# Szymon_Sochaj_schemat2.net
KiCad netlist of a schematic drawn in EAGLE
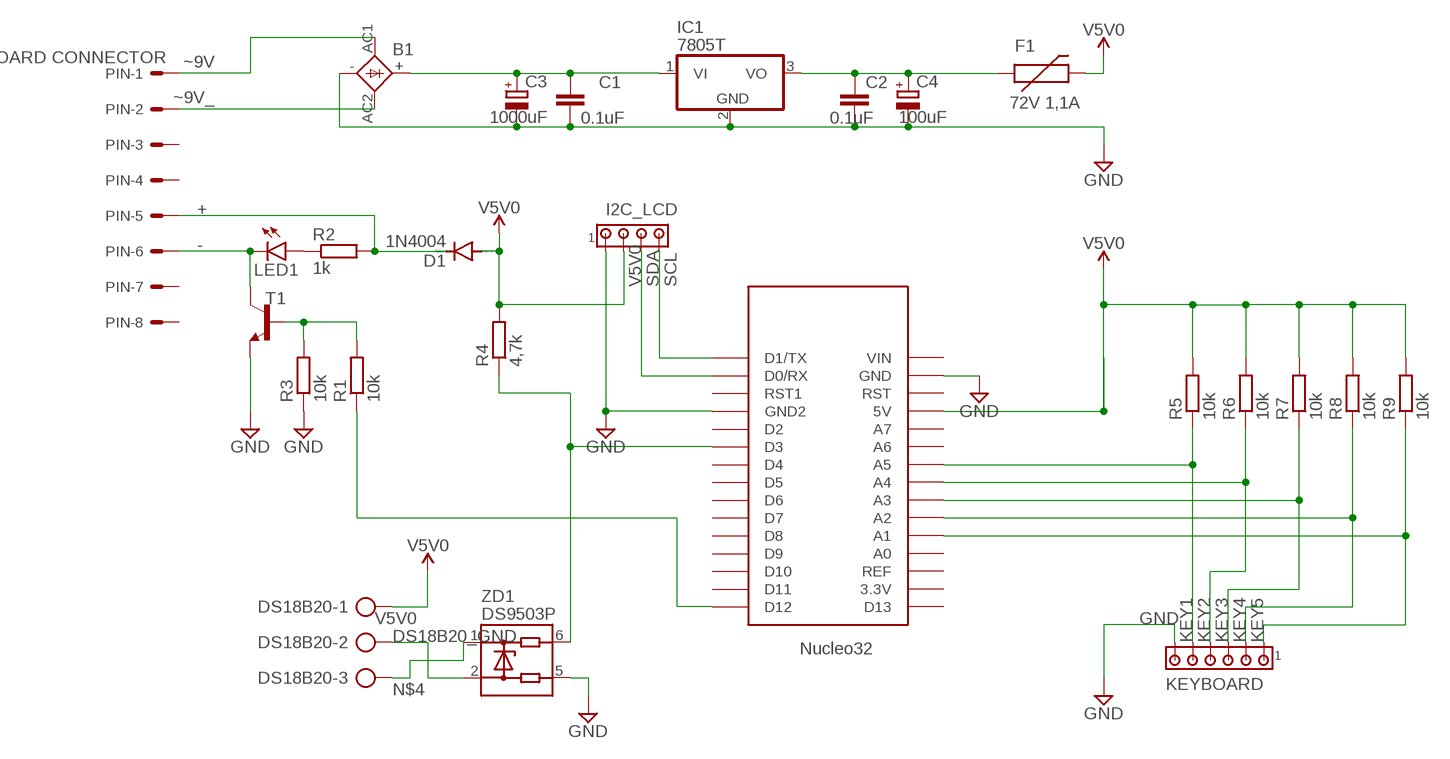
[diagram p0: schematic, sheet 1]

(export (version "E")
  (design (tool "Eeschema 10.0.6"))
  (components
    (comp (ref "B1")
      (value "2KBP")
      (footprint "eagle-import:2KBP")
      (libsource (lib "eagle-import") (part "2KBP"))
    )
    (comp (ref "C1")
      (value "0.1uF")
      (footprint "eagle-import:CAP-PTH-SMALL-KIT")
      (libsource (lib "eagle-import") (part "0.1UF-KIT-EZ-50V-20%"))
    )
    (comp (ref "C2")
      (value "0.1uF")
      (footprint "eagle-import:CAP-PTH-SMALL-KIT")
      (libsource (lib "eagle-import") (part "0.1UF-KIT-EZ-50V-20%"))
    )
    (comp (ref "C3")
      (value "1000uF")
      (footprint "eagle-import:CAPPRD550W60D1200H2000B")
      (libsource (lib "eagle-import") (part "C-POLRADIAL-20MM-DIA"))
    )
    (comp (ref "C4")
      (value "100uF")
      (footprint "eagle-import:CAPPRD550W60D1200H2000B")
      (libsource (lib "eagle-import") (part "C-POLRADIAL-20MM-DIA_"))
    )
    (comp (ref "D1")
      (value "1N4004")
      (footprint "eagle-import:DO41-10")
      (libsource (lib "eagle-import") (part "1N4004"))
    )
    (comp (ref "DS18B20")
      (value "AK300/3")
      (footprint "eagle-import:AK300_3")
      (libsource (lib "eagle-import") (part "AK300/3"))
    )
    (comp (ref "F1")
      (value "72V 1,1A")
      (footprint "eagle-import:PTC")
      (libsource (lib "eagle-import") (part "PTCPTH"))
    )
    (comp (ref "I2C_LCD")
      (value "MTA04-100")
      (footprint "eagle-import:10X04MTA")
      (libsource (lib "eagle-import") (part "MTA04-100"))
    )
    (comp (ref "IC1")
      (value "7805T")
      (footprint "eagle-import:TO220H")
      (libsource (lib "eagle-import") (part "78T05"))
    )
    (comp (ref "KEYBOARD")
      (value "MTA06-100")
      (footprint "eagle-import:10X06MTA")
      (libsource (lib "eagle-import") (part "MTA06-100"))
    )
    (comp (ref "LED1")
      (value "LED3MM")
      (footprint "eagle-import:LED3MM")
      (libsource (lib "eagle-import") (part "LED3MM"))
    )
    (comp (ref "PIN")
      (value "BOARD CONNECTOR")
      (footprint "eagle-import:7395-08")
      (fields (field (name "MF") "MOLEX"))
      (libsource (lib "eagle-import") (part "22-?-0805-7088"))
    )
    (comp (ref "R1")
      (value "10k")
      (footprint "eagle-import:0204_5")
      (libsource (lib "eagle-import") (part "R-EU_0204/5"))
    )
    (comp (ref "R2")
      (value "1k")
      (footprint "eagle-import:0204_5")
      (libsource (lib "eagle-import") (part "R-EU_0204/5"))
    )
    (comp (ref "R3")
      (value "10k")
      (footprint "eagle-import:0204_5")
      (libsource (lib "eagle-import") (part "R-EU_0204/5"))
    )
    (comp (ref "R4")
      (value "4,7k")
      (footprint "eagle-import:0204_5")
      (libsource (lib "eagle-import") (part "R-EU_0204/5"))
    )
    (comp (ref "R5")
      (value "10k")
      (footprint "eagle-import:0204_5")
      (libsource (lib "eagle-import") (part "R-EU_0204/5"))
    )
    (comp (ref "R6")
      (value "10k")
      (footprint "eagle-import:0204_5")
      (libsource (lib "eagle-import") (part "R-EU_0204/5"))
    )
    (comp (ref "R7")
      (value "10k")
      (footprint "eagle-import:0204_5")
      (libsource (lib "eagle-import") (part "R-EU_0204/5"))
    )
    (comp (ref "R8")
      (value "10k")
      (footprint "eagle-import:0204_5")
      (libsource (lib "eagle-import") (part "R-EU_0204/5"))
    )
    (comp (ref "R9")
      (value "10k")
      (footprint "eagle-import:0204_5")
      (libsource (lib "eagle-import") (part "R-EU_0204/5"))
    )
    (comp (ref "T1")
      (value "BC337")
      (footprint "eagle-import:TO92-ECB")
      (libsource (lib "eagle-import") (part "2SC1740"))
    )
    (comp (ref "U$1")
      (value "NUCLEO32")
      (footprint "eagle-import:NUCLEO32")
      (libsource (lib "eagle-import") (part "NUCLEO32"))
    )
    (comp (ref "ZD1")
      (value "DS9503P")
      (footprint "eagle-import:TSOC6")
      (libsource (lib "eagle-import") (part "DS9503P"))
    )
  )
  (nets
    (net (code "1") (name "/+") (class "Default")
      (node (ref "D1") (pin "C") (pinfunction "C_C") (pintype "passive"))
      (node (ref "PIN") (pin "5") (pinfunction "S_5") (pintype "passive"))
      (node (ref "R2") (pin "2") (pinfunction "2_2") (pintype "passive"))
    )
    (net (code "2") (name "/-") (class "Default")
      (node (ref "LED1") (pin "K") (pinfunction "C_K") (pintype "passive"))
      (node (ref "PIN") (pin "6") (pinfunction "S_6") (pintype "passive"))
      (node (ref "T1") (pin "C") (pinfunction "B_C") (pintype "passive"))
    )
    (net (code "3") (name "/DS18B20_GND") (class "Default")
      (node (ref "DS18B20") (pin "2") (pinfunction "KL_2") (pintype "passive"))
      (node (ref "ZD1") (pin "2") (pinfunction "P$2_2") (pintype "passive"))
    )
    (net (code "4") (name "/KEY1") (class "Default")
      (node (ref "KEYBOARD") (pin "5") (pinfunction "5_5") (pintype "passive"))
      (node (ref "R5") (pin "1") (pinfunction "1_1") (pintype "passive"))
      (node (ref "U$1") (pin "A5") (pinfunction "A5_A5") (pintype "bidirectional"))
    )
    (net (code "5") (name "/KEY2") (class "Default")
      (node (ref "KEYBOARD") (pin "4") (pinfunction "4_4") (pintype "passive"))
      (node (ref "R6") (pin "1") (pinfunction "1_1") (pintype "passive"))
      (node (ref "U$1") (pin "A4") (pinfunction "A4_A4") (pintype "bidirectional"))
    )
    (net (code "6") (name "/KEY3") (class "Default")
      (node (ref "KEYBOARD") (pin "3") (pinfunction "3_3") (pintype "passive"))
      (node (ref "R7") (pin "1") (pinfunction "1_1") (pintype "passive"))
      (node (ref "U$1") (pin "A3") (pinfunction "A3_A3") (pintype "bidirectional"))
    )
    (net (code "7") (name "/KEY4") (class "Default")
      (node (ref "KEYBOARD") (pin "2") (pinfunction "2_2") (pintype "passive"))
      (node (ref "R8") (pin "1") (pinfunction "1_1") (pintype "passive"))
      (node (ref "U$1") (pin "A2") (pinfunction "A2_A2") (pintype "bidirectional"))
    )
    (net (code "8") (name "/KEY5") (class "Default")
      (node (ref "KEYBOARD") (pin "1") (pinfunction "1_1") (pintype "passive"))
      (node (ref "R9") (pin "1") (pinfunction "1_1") (pintype "passive"))
      (node (ref "U$1") (pin "A1") (pinfunction "A1_A1") (pintype "bidirectional"))
    )
    (net (code "9") (name "/N$4") (class "Default")
      (node (ref "DS18B20") (pin "3") (pinfunction "KL_3") (pintype "passive"))
      (node (ref "ZD1") (pin "1") (pinfunction "P$1_1") (pintype "passive"))
    )
    (net (code "10") (name "/SCL") (class "Default")
      (node (ref "I2C_LCD") (pin "4") (pinfunction "4_4") (pintype "passive"))
      (node (ref "U$1") (pin "TX0") (pinfunction "D1/TX_TX0") (pintype "bidirectional"))
    )
    (net (code "11") (name "/SDA") (class "Default")
      (node (ref "I2C_LCD") (pin "3") (pinfunction "3_3") (pintype "passive"))
      (node (ref "U$1") (pin "RX1") (pinfunction "D0/RX_RX1") (pintype "bidirectional"))
    )
    (net (code "12") (name "/~{9V_}") (class "Default")
      (node (ref "B1") (pin "AC2") (pinfunction "AC2_AC2") (pintype "passive"))
      (node (ref "PIN") (pin "2") (pinfunction "S_2") (pintype "passive"))
    )
    (net (code "13") (name "/~{9V}") (class "Default")
      (node (ref "B1") (pin "AC1") (pinfunction "AC1_AC1") (pintype "passive"))
      (node (ref "PIN") (pin "1") (pinfunction "S_1") (pintype "passive"))
    )
    (net (code "14") (name "GND") (class "Default")
      (node (ref "B1") (pin "-") (pinfunction "-_-") (pintype "passive"))
      (node (ref "C1") (pin "2") (pinfunction "2_2") (pintype "passive"))
      (node (ref "C2") (pin "2") (pinfunction "2_2") (pintype "passive"))
      (node (ref "C3") (pin "2") (pinfunction "-_2") (pintype "passive"))
      (node (ref "C4") (pin "2") (pinfunction "-_2") (pintype "passive"))
      (node (ref "I2C_LCD") (pin "1") (pinfunction "1_1") (pintype "passive"))
      (node (ref "IC1") (pin "2") (pinfunction "GND_2") (pintype "passive"))
      (node (ref "KEYBOARD") (pin "6") (pinfunction "6_6") (pintype "passive"))
      (node (ref "R3") (pin "1") (pinfunction "1_1") (pintype "passive"))
      (node (ref "T1") (pin "E") (pinfunction "E_E") (pintype "passive"))
      (node (ref "U$1") (pin "GND") (pinfunction "GND_GND") (pintype "bidirectional"))
      (node (ref "U$1") (pin "GND1") (pinfunction "GND2_GND1") (pintype "bidirectional"))
      (node (ref "ZD1") (pin "5") (pinfunction "P$3_5") (pintype "passive"))
    )
    (net (code "15") (name "Net-(C3-+)") (class "Default")
      (node (ref "B1") (pin "+") (pinfunction "+_+") (pintype "passive"))
      (node (ref "C1") (pin "1") (pinfunction "1_1") (pintype "passive"))
      (node (ref "C3") (pin "1") (pinfunction "+_1") (pintype "passive"))
      (node (ref "IC1") (pin "1") (pinfunction "VI_1") (pintype "input"))
    )
    (net (code "16") (name "Net-(C4-+)") (class "Default")
      (node (ref "C2") (pin "1") (pinfunction "1_1") (pintype "passive"))
      (node (ref "C4") (pin "1") (pinfunction "+_1") (pintype "passive"))
      (node (ref "F1") (pin "P$1") (pinfunction "1_P$1") (pintype "bidirectional"))
      (node (ref "IC1") (pin "3") (pinfunction "VO_3") (pintype "passive"))
    )
    (net (code "17") (name "Net-(LED1-PadA)") (class "Default")
      (node (ref "LED1") (pin "A") (pinfunction "A_A") (pintype "passive"))
      (node (ref "R2") (pin "1") (pinfunction "1_1") (pintype "passive"))
    )
    (net (code "18") (name "Net-(R1-Pad1)") (class "Default")
      (node (ref "R1") (pin "1") (pinfunction "1_1") (pintype "passive"))
      (node (ref "U$1") (pin "D12") (pinfunction "D12_D12") (pintype "bidirectional"))
    )
    (net (code "19") (name "Net-(T1-C)") (class "Default")
      (node (ref "R1") (pin "2") (pinfunction "2_2") (pintype "passive"))
      (node (ref "R3") (pin "2") (pinfunction "2_2") (pintype "passive"))
      (node (ref "T1") (pin "B") (pinfunction "C_B") (pintype "passive"))
    )
    (net (code "20") (name "Net-(ZD1-P$4)") (class "Default")
      (node (ref "R4") (pin "1") (pinfunction "1_1") (pintype "passive"))
      (node (ref "U$1") (pin "D3") (pinfunction "D3_D3") (pintype "bidirectional"))
      (node (ref "ZD1") (pin "6") (pinfunction "P$4_6") (pintype "passive"))
    )
    (net (code "21") (name "V5V0") (class "Default")
      (node (ref "D1") (pin "A") (pinfunction "A_A") (pintype "passive"))
      (node (ref "DS18B20") (pin "1") (pinfunction "KL_1") (pintype "passive"))
      (node (ref "F1") (pin "P$2") (pinfunction "2_P$2") (pintype "bidirectional"))
      (node (ref "I2C_LCD") (pin "2") (pinfunction "2_2") (pintype "passive"))
      (node (ref "R4") (pin "2") (pinfunction "2_2") (pintype "passive"))
      (node (ref "R5") (pin "2") (pinfunction "2_2") (pintype "passive"))
      (node (ref "R6") (pin "2") (pinfunction "2_2") (pintype "passive"))
      (node (ref "R7") (pin "2") (pinfunction "2_2") (pintype "passive"))
      (node (ref "R8") (pin "2") (pinfunction "2_2") (pintype "passive"))
      (node (ref "R9") (pin "2") (pinfunction "2_2") (pintype "passive"))
      (node (ref "U$1") (pin "5V") (pinfunction "5V_5V") (pintype "bidirectional"))
    )
    (net (code "22") (name "unconnected-(PINC-S-Pad3)") (class "Default")
      (node (ref "PIN") (pin "3") (pinfunction "S_3") (pintype "passive"))
    )
    (net (code "23") (name "unconnected-(PIND-S-Pad4)") (class "Default")
      (node (ref "PIN") (pin "4") (pinfunction "S_4") (pintype "passive"))
    )
    (net (code "24") (name "unconnected-(PING-S-Pad7)") (class "Default")
      (node (ref "PIN") (pin "7") (pinfunction "S_7") (pintype "passive"))
    )
    (net (code "25") (name "unconnected-(PINH-S-Pad8)") (class "Default")
      (node (ref "PIN") (pin "8") (pinfunction "S_8") (pintype "passive"))
    )
    (net (code "26") (name "unconnected-(U$1-Pad3.3V)") (class "Default")
      (node (ref "U$1") (pin "3.3V") (pinfunction "3.3V_3.3V") (pintype "bidirectional"))
    )
    (net (code "27") (name "unconnected-(U$1-PadA0)") (class "Default")
      (node (ref "U$1") (pin "A0") (pinfunction "A0_A0") (pintype "bidirectional"))
    )
    (net (code "28") (name "unconnected-(U$1-PadA6)") (class "Default")
      (node (ref "U$1") (pin "A6") (pinfunction "A6_A6") (pintype "bidirectional"))
    )
    (net (code "29") (name "unconnected-(U$1-PadA7)") (class "Default")
      (node (ref "U$1") (pin "A7") (pinfunction "A7_A7") (pintype "bidirectional"))
    )
    (net (code "30") (name "unconnected-(U$1-PadD2)") (class "Default")
      (node (ref "U$1") (pin "D2") (pinfunction "D2_D2") (pintype "bidirectional"))
    )
    (net (code "31") (name "unconnected-(U$1-PadD4)") (class "Default")
      (node (ref "U$1") (pin "D4") (pinfunction "D4_D4") (pintype "bidirectional"))
    )
    (net (code "32") (name "unconnected-(U$1-PadD5)") (class "Default")
      (node (ref "U$1") (pin "D5") (pinfunction "D5_D5") (pintype "bidirectional"))
    )
    (net (code "33") (name "unconnected-(U$1-PadD6)") (class "Default")
      (node (ref "U$1") (pin "D6") (pinfunction "D6_D6") (pintype "bidirectional"))
    )
    (net (code "34") (name "unconnected-(U$1-PadD7)") (class "Default")
      (node (ref "U$1") (pin "D7") (pinfunction "D7_D7") (pintype "bidirectional"))
    )
    (net (code "35") (name "unconnected-(U$1-PadD8)") (class "Default")
      (node (ref "U$1") (pin "D8") (pinfunction "D8_D8") (pintype "bidirectional"))
    )
    (net (code "36") (name "unconnected-(U$1-PadD9)") (class "Default")
      (node (ref "U$1") (pin "D9") (pinfunction "D9_D9") (pintype "bidirectional"))
    )
    (net (code "37") (name "unconnected-(U$1-PadD10)") (class "Default")
      (node (ref "U$1") (pin "D10") (pinfunction "D10_D10") (pintype "bidirectional"))
    )
    (net (code "38") (name "unconnected-(U$1-PadD11)") (class "Default")
      (node (ref "U$1") (pin "D11") (pinfunction "D11_D11") (pintype "bidirectional"))
    )
    (net (code "39") (name "unconnected-(U$1-PadD13)") (class "Default")
      (node (ref "U$1") (pin "D13") (pinfunction "D13_D13") (pintype "bidirectional"))
    )
    (net (code "40") (name "unconnected-(U$1-PadICSP1)") (class "Default")
      (node (ref "U$1") (pin "ICSP1") (pinfunction "ICSP1_ICSP1") (pintype "bidirectional"))
    )
    (net (code "41") (name "unconnected-(U$1-PadICSP2)") (class "Default")
      (node (ref "U$1") (pin "ICSP2") (pinfunction "ICSP2_ICSP2") (pintype "bidirectional"))
    )
    (net (code "42") (name "unconnected-(U$1-PadICSP3)") (class "Default")
      (node (ref "U$1") (pin "ICSP3") (pinfunction "ICSP3_ICSP3") (pintype "bidirectional"))
    )
    (net (code "43") (name "unconnected-(U$1-PadICSP4)") (class "Default")
      (node (ref "U$1") (pin "ICSP4") (pinfunction "ICSP4_ICSP4") (pintype "bidirectional"))
    )
    (net (code "44") (name "unconnected-(U$1-PadICSP5)") (class "Default")
      (node (ref "U$1") (pin "ICSP5") (pinfunction "ICSP5_ICSP5") (pintype "bidirectional"))
    )
    (net (code "45") (name "unconnected-(U$1-PadICSP6)") (class "Default")
      (node (ref "U$1") (pin "ICSP6") (pinfunction "ICSP6_ICSP6") (pintype "bidirectional"))
    )
    (net (code "46") (name "unconnected-(U$1-PadRST)") (class "Default")
      (node (ref "U$1") (pin "RST") (pinfunction "RST_RST") (pintype "bidirectional"))
    )
    (net (code "47") (name "unconnected-(U$1-PadRST1)") (class "Default")
      (node (ref "U$1") (pin "RST1") (pinfunction "RST1_RST1") (pintype "bidirectional"))
    )
    (net (code "48") (name "unconnected-(U$1-REF-PadAREF)") (class "Default")
      (node (ref "U$1") (pin "AREF") (pinfunction "REF_AREF") (pintype "bidirectional"))
    )
    (net (code "49") (name "unconnected-(U$1-VIN-PadRAW)") (class "Default")
      (node (ref "U$1") (pin "RAW") (pinfunction "VIN_RAW") (pintype "bidirectional"))
    )
  )
)
